# laztech.net
KiCad netlist of a schematic drawn in EAGLE
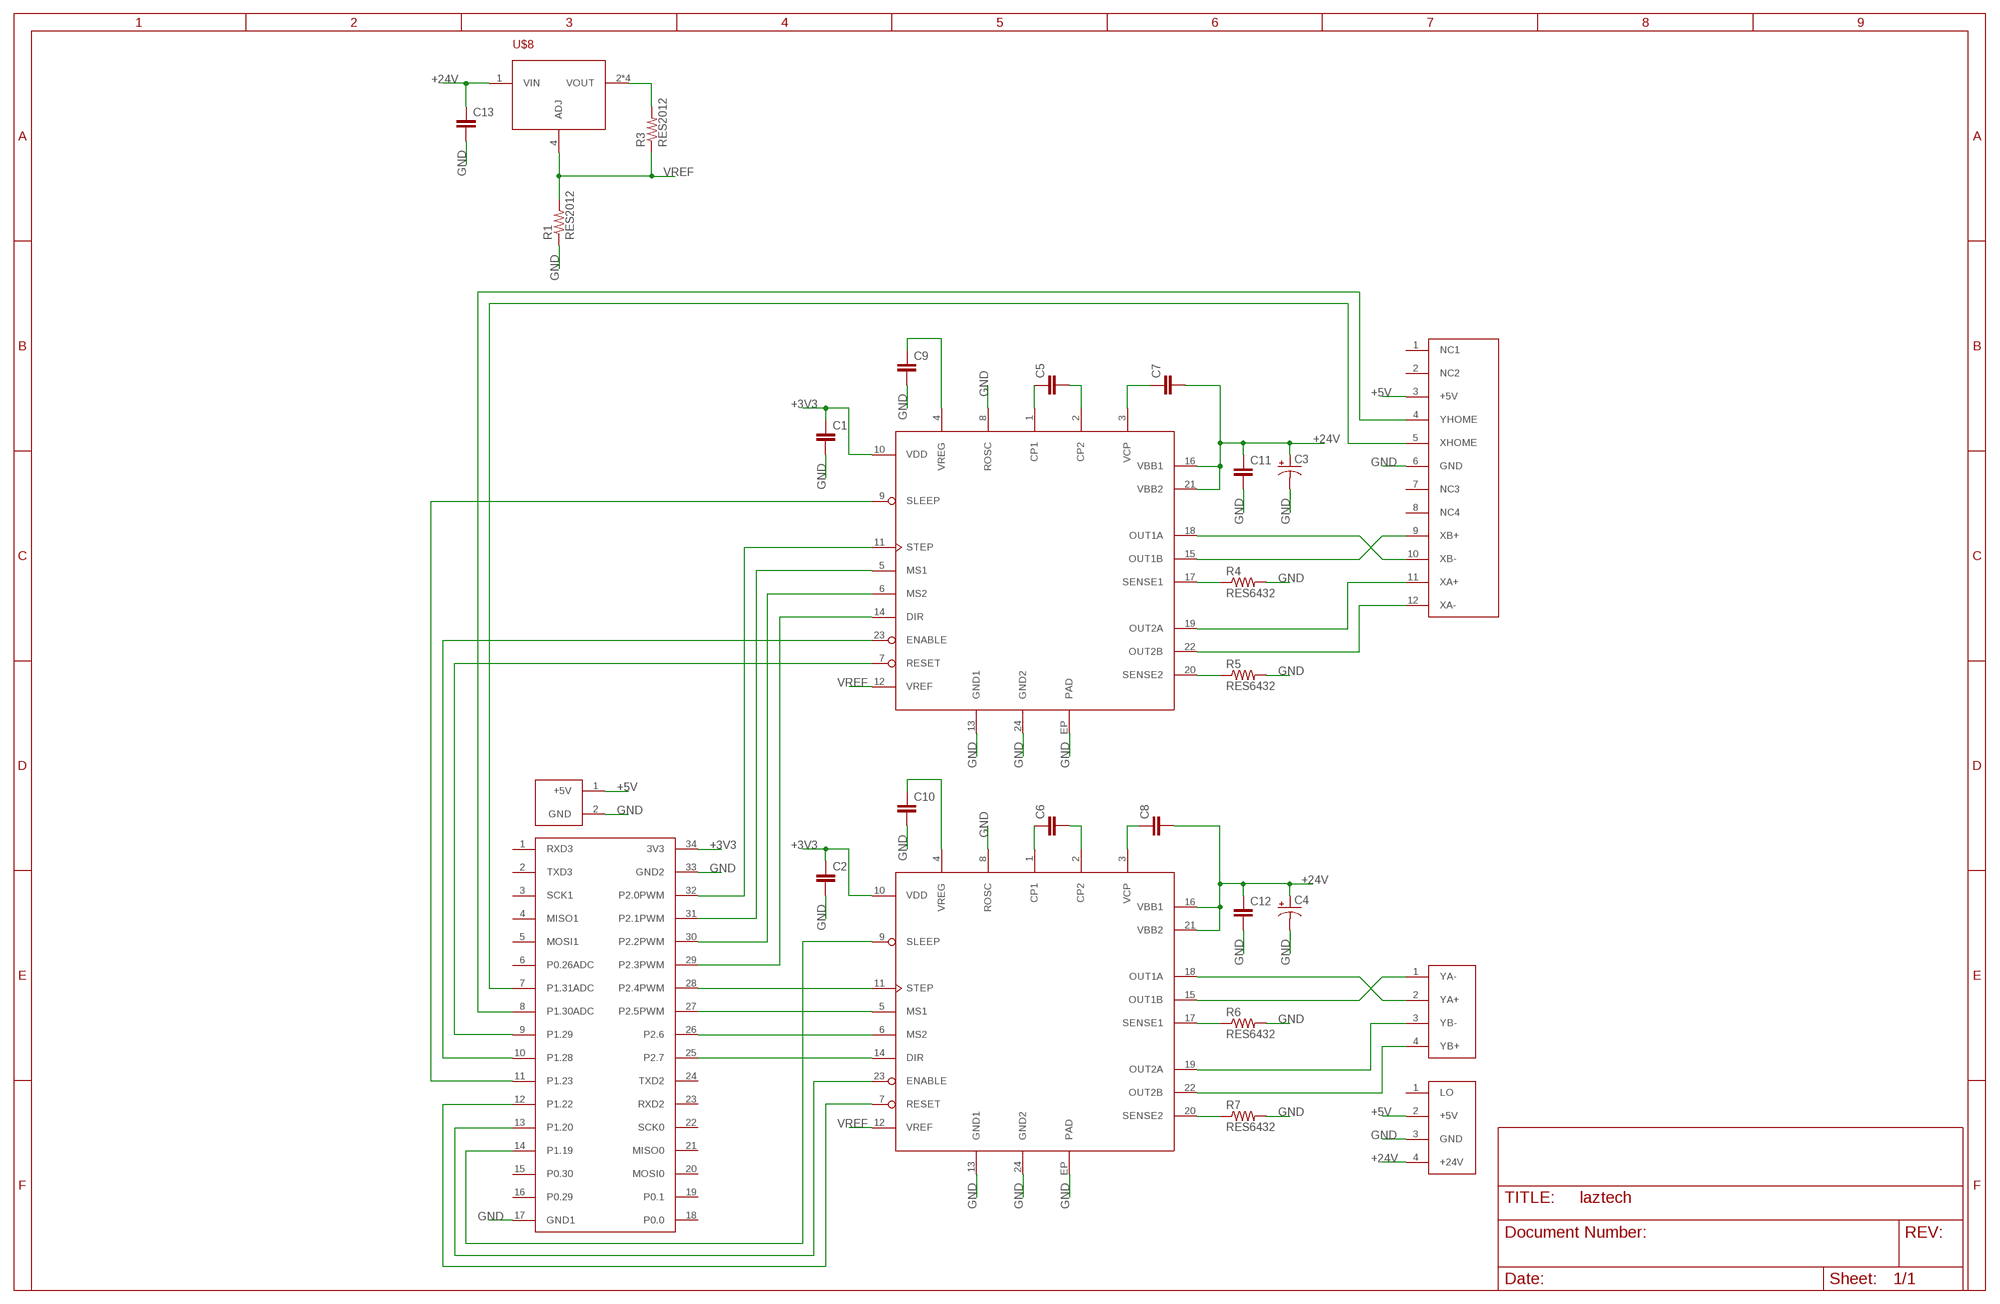
[diagram p0: schematic, sheet 1]

(export (version "E")
  (design (tool "Eeschema 10.0.6"))
  (components
    (comp (ref "C1")
      (value "CAP")
      (footprint "eagle-import:C2012")
      (libsource (lib "eagle-import") (part "CAP"))
    )
    (comp (ref "C2")
      (value "CAP")
      (footprint "eagle-import:C2012")
      (libsource (lib "eagle-import") (part "CAP"))
    )
    (comp (ref "C3")
      (value "PCAP")
      (footprint "eagle-import:C6358R")
      (libsource (lib "eagle-import") (part "PCAP"))
    )
    (comp (ref "C4")
      (value "PCAP")
      (footprint "eagle-import:C6358R")
      (libsource (lib "eagle-import") (part "PCAP"))
    )
    (comp (ref "C5")
      (value "CAP")
      (footprint "eagle-import:C2012")
      (libsource (lib "eagle-import") (part "CAP"))
    )
    (comp (ref "C6")
      (value "CAP")
      (footprint "eagle-import:C2012")
      (libsource (lib "eagle-import") (part "CAP"))
    )
    (comp (ref "C7")
      (value "CAP")
      (footprint "eagle-import:C2012")
      (libsource (lib "eagle-import") (part "CAP"))
    )
    (comp (ref "C8")
      (value "CAP")
      (footprint "eagle-import:C2012")
      (libsource (lib "eagle-import") (part "CAP"))
    )
    (comp (ref "C9")
      (value "CAP")
      (footprint "eagle-import:C2012")
      (libsource (lib "eagle-import") (part "CAP"))
    )
    (comp (ref "C10")
      (value "CAP")
      (footprint "eagle-import:C2012")
      (libsource (lib "eagle-import") (part "CAP"))
    )
    (comp (ref "C11")
      (value "CAP")
      (footprint "eagle-import:C2012")
      (libsource (lib "eagle-import") (part "CAP"))
    )
    (comp (ref "C12")
      (value "CAP")
      (footprint "eagle-import:C2012")
      (libsource (lib "eagle-import") (part "CAP"))
    )
    (comp (ref "C13")
      (value "CAP")
      (footprint "eagle-import:C2012")
      (libsource (lib "eagle-import") (part "CAP"))
    )
    (comp (ref "R1")
      (value "RES2012")
      (footprint "eagle-import:R2012")
      (libsource (lib "eagle-import") (part "RES2012"))
    )
    (comp (ref "R3")
      (value "RES2012")
      (footprint "eagle-import:R2012")
      (libsource (lib "eagle-import") (part "RES2012"))
    )
    (comp (ref "R4")
      (value "RES6432")
      (footprint "eagle-import:R6432")
      (libsource (lib "eagle-import") (part "RES6432"))
    )
    (comp (ref "R5")
      (value "RES6432")
      (footprint "eagle-import:R6432")
      (libsource (lib "eagle-import") (part "RES6432"))
    )
    (comp (ref "R6")
      (value "RES6432")
      (footprint "eagle-import:R6432")
      (libsource (lib "eagle-import") (part "RES6432"))
    )
    (comp (ref "R7")
      (value "RES6432")
      (footprint "eagle-import:R6432")
      (libsource (lib "eagle-import") (part "RES6432"))
    )
    (comp (ref "U$1")
      (value "A4985SLPTR-T")
      (footprint "eagle-import:ETSSOP-24")
      (libsource (lib "eagle-import") (part "A4985SLPTR-T"))
    )
    (comp (ref "U$2")
      (value "A4985SLPTR-T")
      (footprint "eagle-import:ETSSOP-24")
      (libsource (lib "eagle-import") (part "A4985SLPTR-T"))
    )
    (comp (ref "U$3")
      (value "SJSUONEX")
      (footprint "eagle-import:2X17")
      (libsource (lib "eagle-import") (part "SJSUONEX"))
    )
    (comp (ref "U$4")
      (value "K40-PWR")
      (footprint "eagle-import:MOLEX-KK396-4-RA")
      (libsource (lib "eagle-import") (part "K40-PWR"))
    )
    (comp (ref "U$5")
      (value "K40-X")
      (footprint "eagle-import:MOLEX-FFC-12-RA")
      (libsource (lib "eagle-import") (part "K40-X"))
    )
    (comp (ref "U$6")
      (value "K40-Y")
      (footprint "eagle-import:JST-XH-4_RA")
      (libsource (lib "eagle-import") (part "K40-Y"))
    )
    (comp (ref "U$7")
      (value "SJSUONEVIN")
      (footprint "eagle-import:1X02")
      (libsource (lib "eagle-import") (part "SJSUONEVIN"))
    )
    (comp (ref "U$8")
      (value "LM317")
      (footprint "eagle-import:SOIC-8")
      (libsource (lib "eagle-import") (part "LM317"))
    )
  )
  (nets
    (net (code "1") (name "/+3V3") (class "Default")
      (node (ref "C1") (pin "1") (pinfunction "1_1") (pintype "passive"))
      (node (ref "C2") (pin "1") (pinfunction "1_1") (pintype "passive"))
      (node (ref "U$1") (pin "10") (pinfunction "VDD_10") (pintype "power_in"))
      (node (ref "U$2") (pin "10") (pinfunction "VDD_10") (pintype "power_in"))
      (node (ref "U$3") (pin "34") (pinfunction "3V3_34") (pintype "power_in"))
    )
    (net (code "2") (name "/+5V") (class "Default")
      (node (ref "U$4") (pin "2") (pinfunction "+5V_2") (pintype "power_in"))
      (node (ref "U$5") (pin "3") (pinfunction "+5V_3") (pintype "power_in"))
      (node (ref "U$7") (pin "1") (pinfunction "+5V_1") (pintype "power_in"))
    )
    (net (code "3") (name "/+24V") (class "Default")
      (node (ref "C11") (pin "1") (pinfunction "1_1") (pintype "passive"))
      (node (ref "C12") (pin "1") (pinfunction "1_1") (pintype "passive"))
      (node (ref "C13") (pin "1") (pinfunction "1_1") (pintype "passive"))
      (node (ref "C3") (pin "2") (pinfunction "+_2") (pintype "passive"))
      (node (ref "C4") (pin "2") (pinfunction "+_2") (pintype "passive"))
      (node (ref "C7") (pin "2") (pinfunction "2_2") (pintype "passive"))
      (node (ref "C8") (pin "2") (pinfunction "2_2") (pintype "passive"))
      (node (ref "U$1") (pin "16") (pinfunction "VBB1_16") (pintype "bidirectional"))
      (node (ref "U$1") (pin "21") (pinfunction "VBB2_21") (pintype "bidirectional"))
      (node (ref "U$2") (pin "16") (pinfunction "VBB1_16") (pintype "bidirectional"))
      (node (ref "U$2") (pin "21") (pinfunction "VBB2_21") (pintype "bidirectional"))
      (node (ref "U$4") (pin "4") (pinfunction "+24V_4") (pintype "power_in"))
      (node (ref "U$8") (pin "1") (pinfunction "VIN_1") (pintype "power_in"))
    )
    (net (code "4") (name "/GND") (class "Default")
      (node (ref "C1") (pin "2") (pinfunction "2_2") (pintype "passive"))
      (node (ref "C10") (pin "2") (pinfunction "2_2") (pintype "passive"))
      (node (ref "C11") (pin "2") (pinfunction "2_2") (pintype "passive"))
      (node (ref "C12") (pin "2") (pinfunction "2_2") (pintype "passive"))
      (node (ref "C13") (pin "2") (pinfunction "2_2") (pintype "passive"))
      (node (ref "C2") (pin "2") (pinfunction "2_2") (pintype "passive"))
      (node (ref "C3") (pin "1") (pinfunction "-_1") (pintype "passive"))
      (node (ref "C4") (pin "1") (pinfunction "-_1") (pintype "passive"))
      (node (ref "C9") (pin "2") (pinfunction "2_2") (pintype "passive"))
      (node (ref "R1") (pin "1") (pinfunction "1_1") (pintype "passive"))
      (node (ref "R4") (pin "2") (pinfunction "2_2") (pintype "passive"))
      (node (ref "R5") (pin "2") (pinfunction "2_2") (pintype "passive"))
      (node (ref "R6") (pin "2") (pinfunction "2_2") (pintype "passive"))
      (node (ref "R7") (pin "2") (pinfunction "2_2") (pintype "passive"))
      (node (ref "U$1") (pin "13") (pinfunction "GND1_13") (pintype "power_in"))
      (node (ref "U$1") (pin "24") (pinfunction "GND2_24") (pintype "power_in"))
      (node (ref "U$1") (pin "8") (pinfunction "ROSC_8") (pintype "bidirectional"))
      (node (ref "U$1") (pin "EP") (pinfunction "PAD_EP") (pintype "power_in"))
      (node (ref "U$2") (pin "13") (pinfunction "GND1_13") (pintype "power_in"))
      (node (ref "U$2") (pin "24") (pinfunction "GND2_24") (pintype "power_in"))
      (node (ref "U$2") (pin "8") (pinfunction "ROSC_8") (pintype "bidirectional"))
      (node (ref "U$2") (pin "EP") (pinfunction "PAD_EP") (pintype "power_in"))
      (node (ref "U$3") (pin "17") (pinfunction "GND1_17") (pintype "power_in"))
      (node (ref "U$3") (pin "33") (pinfunction "GND2_33") (pintype "power_in"))
      (node (ref "U$4") (pin "3") (pinfunction "GND_3") (pintype "power_in"))
      (node (ref "U$5") (pin "6") (pinfunction "GND_6") (pintype "power_in"))
      (node (ref "U$7") (pin "2") (pinfunction "GND_2") (pintype "power_in"))
    )
    (net (code "5") (name "/VREF") (class "Default")
      (node (ref "R1") (pin "2") (pinfunction "2_2") (pintype "passive"))
      (node (ref "R3") (pin "1") (pinfunction "1_1") (pintype "passive"))
      (node (ref "U$1") (pin "12") (pinfunction "VREF_12") (pintype "input"))
      (node (ref "U$2") (pin "12") (pinfunction "VREF_12") (pintype "input"))
      (node (ref "U$8") (pin "4") (pinfunction "ADJ_4") (pintype "input"))
    )
    (net (code "6") (name "Net-(R3-Pad2)") (class "Default")
      (node (ref "R3") (pin "2") (pinfunction "2_2") (pintype "passive"))
      (node (ref "U$8") (pin "2") (pinfunction "VOUT_2") (pintype "output"))
      (node (ref "U$8") (pin "3") (pinfunction "VOUT_3") (pintype "output"))
      (node (ref "U$8") (pin "6") (pinfunction "VOUT_6") (pintype "output"))
      (node (ref "U$8") (pin "7") (pinfunction "VOUT_7") (pintype "output"))
    )
    (net (code "7") (name "Net-(U$1-CP1)") (class "Default")
      (node (ref "C5") (pin "1") (pinfunction "1_1") (pintype "passive"))
      (node (ref "U$1") (pin "1") (pinfunction "CP1_1") (pintype "bidirectional"))
    )
    (net (code "8") (name "Net-(U$1-CP2)") (class "Default")
      (node (ref "C5") (pin "2") (pinfunction "2_2") (pintype "passive"))
      (node (ref "U$1") (pin "2") (pinfunction "CP2_2") (pintype "bidirectional"))
    )
    (net (code "9") (name "Net-(U$1-DIR)") (class "Default")
      (node (ref "U$1") (pin "14") (pinfunction "DIR_14") (pintype "input"))
      (node (ref "U$3") (pin "29") (pinfunction "P2.3PWM_29") (pintype "bidirectional"))
    )
    (net (code "10") (name "Net-(U$1-ENABLE)") (class "Default")
      (node (ref "U$1") (pin "23") (pinfunction "ENABLE_23") (pintype "input"))
      (node (ref "U$3") (pin "10") (pinfunction "P1.28_10") (pintype "bidirectional"))
    )
    (net (code "11") (name "Net-(U$1-MS1)") (class "Default")
      (node (ref "U$1") (pin "5") (pinfunction "MS1_5") (pintype "input"))
      (node (ref "U$3") (pin "31") (pinfunction "P2.1PWM_31") (pintype "bidirectional"))
    )
    (net (code "12") (name "Net-(U$1-MS2)") (class "Default")
      (node (ref "U$1") (pin "6") (pinfunction "MS2_6") (pintype "input"))
      (node (ref "U$3") (pin "30") (pinfunction "P2.2PWM_30") (pintype "bidirectional"))
    )
    (net (code "13") (name "Net-(U$1-OUT1A)") (class "Default")
      (node (ref "U$1") (pin "18") (pinfunction "OUT1A_18") (pintype "bidirectional"))
      (node (ref "U$5") (pin "10") (pinfunction "XB-_10") (pintype "passive"))
    )
    (net (code "14") (name "Net-(U$1-OUT1B)") (class "Default")
      (node (ref "U$1") (pin "15") (pinfunction "OUT1B_15") (pintype "bidirectional"))
      (node (ref "U$5") (pin "9") (pinfunction "XB+_9") (pintype "passive"))
    )
    (net (code "15") (name "Net-(U$1-OUT2A)") (class "Default")
      (node (ref "U$1") (pin "19") (pinfunction "OUT2A_19") (pintype "bidirectional"))
      (node (ref "U$5") (pin "11") (pinfunction "XA+_11") (pintype "passive"))
    )
    (net (code "16") (name "Net-(U$1-OUT2B)") (class "Default")
      (node (ref "U$1") (pin "22") (pinfunction "OUT2B_22") (pintype "bidirectional"))
      (node (ref "U$5") (pin "12") (pinfunction "XA-_12") (pintype "passive"))
    )
    (net (code "17") (name "Net-(U$1-RESET)") (class "Default")
      (node (ref "U$1") (pin "7") (pinfunction "RESET_7") (pintype "input"))
      (node (ref "U$3") (pin "9") (pinfunction "P1.29_9") (pintype "bidirectional"))
    )
    (net (code "18") (name "Net-(U$1-SENSE1)") (class "Default")
      (node (ref "R4") (pin "1") (pinfunction "1_1") (pintype "passive"))
      (node (ref "U$1") (pin "17") (pinfunction "SENSE1_17") (pintype "bidirectional"))
    )
    (net (code "19") (name "Net-(U$1-SENSE2)") (class "Default")
      (node (ref "R5") (pin "1") (pinfunction "1_1") (pintype "passive"))
      (node (ref "U$1") (pin "20") (pinfunction "SENSE2_20") (pintype "bidirectional"))
    )
    (net (code "20") (name "Net-(U$1-SLEEP)") (class "Default")
      (node (ref "U$1") (pin "9") (pinfunction "SLEEP_9") (pintype "input"))
      (node (ref "U$3") (pin "11") (pinfunction "P1.23_11") (pintype "bidirectional"))
    )
    (net (code "21") (name "Net-(U$1-STEP)") (class "Default")
      (node (ref "U$1") (pin "11") (pinfunction "STEP_11") (pintype "input"))
      (node (ref "U$3") (pin "32") (pinfunction "P2.0PWM_32") (pintype "bidirectional"))
    )
    (net (code "22") (name "Net-(U$1-VCP)") (class "Default")
      (node (ref "C7") (pin "1") (pinfunction "1_1") (pintype "passive"))
      (node (ref "U$1") (pin "3") (pinfunction "VCP_3") (pintype "bidirectional"))
    )
    (net (code "23") (name "Net-(U$1-VREG)") (class "Default")
      (node (ref "C9") (pin "1") (pinfunction "1_1") (pintype "passive"))
      (node (ref "U$1") (pin "4") (pinfunction "VREG_4") (pintype "bidirectional"))
    )
    (net (code "24") (name "Net-(U$2-CP1)") (class "Default")
      (node (ref "C6") (pin "1") (pinfunction "1_1") (pintype "passive"))
      (node (ref "U$2") (pin "1") (pinfunction "CP1_1") (pintype "bidirectional"))
    )
    (net (code "25") (name "Net-(U$2-CP2)") (class "Default")
      (node (ref "C6") (pin "2") (pinfunction "2_2") (pintype "passive"))
      (node (ref "U$2") (pin "2") (pinfunction "CP2_2") (pintype "bidirectional"))
    )
    (net (code "26") (name "Net-(U$2-DIR)") (class "Default")
      (node (ref "U$2") (pin "14") (pinfunction "DIR_14") (pintype "input"))
      (node (ref "U$3") (pin "25") (pinfunction "P2.7_25") (pintype "bidirectional"))
    )
    (net (code "27") (name "Net-(U$2-ENABLE)") (class "Default")
      (node (ref "U$2") (pin "23") (pinfunction "ENABLE_23") (pintype "input"))
      (node (ref "U$3") (pin "13") (pinfunction "P1.20_13") (pintype "bidirectional"))
    )
    (net (code "28") (name "Net-(U$2-MS1)") (class "Default")
      (node (ref "U$2") (pin "5") (pinfunction "MS1_5") (pintype "input"))
      (node (ref "U$3") (pin "27") (pinfunction "P2.5PWM_27") (pintype "bidirectional"))
    )
    (net (code "29") (name "Net-(U$2-MS2)") (class "Default")
      (node (ref "U$2") (pin "6") (pinfunction "MS2_6") (pintype "input"))
      (node (ref "U$3") (pin "26") (pinfunction "P2.6_26") (pintype "bidirectional"))
    )
    (net (code "30") (name "Net-(U$2-OUT1A)") (class "Default")
      (node (ref "U$2") (pin "18") (pinfunction "OUT1A_18") (pintype "bidirectional"))
      (node (ref "U$6") (pin "2") (pinfunction "YA+_2") (pintype "passive"))
    )
    (net (code "31") (name "Net-(U$2-OUT1B)") (class "Default")
      (node (ref "U$2") (pin "15") (pinfunction "OUT1B_15") (pintype "bidirectional"))
      (node (ref "U$6") (pin "1") (pinfunction "YA-_1") (pintype "passive"))
    )
    (net (code "32") (name "Net-(U$2-OUT2A)") (class "Default")
      (node (ref "U$2") (pin "19") (pinfunction "OUT2A_19") (pintype "bidirectional"))
      (node (ref "U$6") (pin "3") (pinfunction "YB-_3") (pintype "passive"))
    )
    (net (code "33") (name "Net-(U$2-OUT2B)") (class "Default")
      (node (ref "U$2") (pin "22") (pinfunction "OUT2B_22") (pintype "bidirectional"))
      (node (ref "U$6") (pin "4") (pinfunction "YB+_4") (pintype "passive"))
    )
    (net (code "34") (name "Net-(U$2-RESET)") (class "Default")
      (node (ref "U$2") (pin "7") (pinfunction "RESET_7") (pintype "input"))
      (node (ref "U$3") (pin "12") (pinfunction "P1.22_12") (pintype "bidirectional"))
    )
    (net (code "35") (name "Net-(U$2-SENSE1)") (class "Default")
      (node (ref "R6") (pin "1") (pinfunction "1_1") (pintype "passive"))
      (node (ref "U$2") (pin "17") (pinfunction "SENSE1_17") (pintype "bidirectional"))
    )
    (net (code "36") (name "Net-(U$2-SENSE2)") (class "Default")
      (node (ref "R7") (pin "1") (pinfunction "1_1") (pintype "passive"))
      (node (ref "U$2") (pin "20") (pinfunction "SENSE2_20") (pintype "bidirectional"))
    )
    (net (code "37") (name "Net-(U$2-SLEEP)") (class "Default")
      (node (ref "U$2") (pin "9") (pinfunction "SLEEP_9") (pintype "input"))
      (node (ref "U$3") (pin "14") (pinfunction "P1.19_14") (pintype "bidirectional"))
    )
    (net (code "38") (name "Net-(U$2-STEP)") (class "Default")
      (node (ref "U$2") (pin "11") (pinfunction "STEP_11") (pintype "input"))
      (node (ref "U$3") (pin "28") (pinfunction "P2.4PWM_28") (pintype "bidirectional"))
    )
    (net (code "39") (name "Net-(U$2-VCP)") (class "Default")
      (node (ref "C8") (pin "1") (pinfunction "1_1") (pintype "passive"))
      (node (ref "U$2") (pin "3") (pinfunction "VCP_3") (pintype "bidirectional"))
    )
    (net (code "40") (name "Net-(U$2-VREG)") (class "Default")
      (node (ref "C10") (pin "1") (pinfunction "1_1") (pintype "passive"))
      (node (ref "U$2") (pin "4") (pinfunction "VREG_4") (pintype "bidirectional"))
    )
    (net (code "41") (name "Net-(U$3-P1.30ADC)") (class "Default")
      (node (ref "U$3") (pin "8") (pinfunction "P1.30ADC_8") (pintype "bidirectional"))
      (node (ref "U$5") (pin "4") (pinfunction "YHOME_4") (pintype "output"))
    )
    (net (code "42") (name "Net-(U$3-P1.31ADC)") (class "Default")
      (node (ref "U$3") (pin "7") (pinfunction "P1.31ADC_7") (pintype "bidirectional"))
      (node (ref "U$5") (pin "5") (pinfunction "XHOME_5") (pintype "output"))
    )
    (net (code "43") (name "unconnected-(U$3-MISO0-Pad21)") (class "Default")
      (node (ref "U$3") (pin "21") (pinfunction "MISO0_21") (pintype "bidirectional"))
    )
    (net (code "44") (name "unconnected-(U$3-MISO1-Pad4)") (class "Default")
      (node (ref "U$3") (pin "4") (pinfunction "MISO1_4") (pintype "bidirectional"))
    )
    (net (code "45") (name "unconnected-(U$3-MOSI0-Pad20)") (class "Default")
      (node (ref "U$3") (pin "20") (pinfunction "MOSI0_20") (pintype "bidirectional"))
    )
    (net (code "46") (name "unconnected-(U$3-MOSI1-Pad5)") (class "Default")
      (node (ref "U$3") (pin "5") (pinfunction "MOSI1_5") (pintype "bidirectional"))
    )
    (net (code "47") (name "unconnected-(U$3-P0.0-Pad18)") (class "Default")
      (node (ref "U$3") (pin "18") (pinfunction "P0.0_18") (pintype "bidirectional"))
    )
    (net (code "48") (name "unconnected-(U$3-P0.1-Pad19)") (class "Default")
      (node (ref "U$3") (pin "19") (pinfunction "P0.1_19") (pintype "bidirectional"))
    )
    (net (code "49") (name "unconnected-(U$3-P0.26ADC-Pad6)") (class "Default")
      (node (ref "U$3") (pin "6") (pinfunction "P0.26ADC_6") (pintype "bidirectional"))
    )
    (net (code "50") (name "unconnected-(U$3-P0.29-Pad16)") (class "Default")
      (node (ref "U$3") (pin "16") (pinfunction "P0.29_16") (pintype "bidirectional"))
    )
    (net (code "51") (name "unconnected-(U$3-P0.30-Pad15)") (class "Default")
      (node (ref "U$3") (pin "15") (pinfunction "P0.30_15") (pintype "bidirectional"))
    )
    (net (code "52") (name "unconnected-(U$3-RXD2-Pad23)") (class "Default")
      (node (ref "U$3") (pin "23") (pinfunction "RXD2_23") (pintype "bidirectional"))
    )
    (net (code "53") (name "unconnected-(U$3-RXD3-Pad1)") (class "Default")
      (node (ref "U$3") (pin "1") (pinfunction "RXD3_1") (pintype "bidirectional"))
    )
    (net (code "54") (name "unconnected-(U$3-SCK0-Pad22)") (class "Default")
      (node (ref "U$3") (pin "22") (pinfunction "SCK0_22") (pintype "bidirectional"))
    )
    (net (code "55") (name "unconnected-(U$3-SCK1-Pad3)") (class "Default")
      (node (ref "U$3") (pin "3") (pinfunction "SCK1_3") (pintype "bidirectional"))
    )
    (net (code "56") (name "unconnected-(U$3-TXD2-Pad24)") (class "Default")
      (node (ref "U$3") (pin "24") (pinfunction "TXD2_24") (pintype "bidirectional"))
    )
    (net (code "57") (name "unconnected-(U$3-TXD3-Pad2)") (class "Default")
      (node (ref "U$3") (pin "2") (pinfunction "TXD3_2") (pintype "bidirectional"))
    )
    (net (code "58") (name "unconnected-(U$4-LO-Pad1)") (class "Default")
      (node (ref "U$4") (pin "1") (pinfunction "LO_1") (pintype "input"))
    )
    (net (code "59") (name "unconnected-(U$5-NC1-Pad1)") (class "Default")
      (node (ref "U$5") (pin "1") (pinfunction "NC1_1") (pintype "no_connect"))
    )
    (net (code "60") (name "unconnected-(U$5-NC2-Pad2)") (class "Default")
      (node (ref "U$5") (pin "2") (pinfunction "NC2_2") (pintype "no_connect"))
    )
    (net (code "61") (name "unconnected-(U$5-NC3-Pad7)") (class "Default")
      (node (ref "U$5") (pin "7") (pinfunction "NC3_7") (pintype "no_connect"))
    )
    (net (code "62") (name "unconnected-(U$5-NC4-Pad8)") (class "Default")
      (node (ref "U$5") (pin "8") (pinfunction "NC4_8") (pintype "no_connect"))
    )
  )
)
